# working.net
KiCad netlist of a schematic drawn in EAGLE
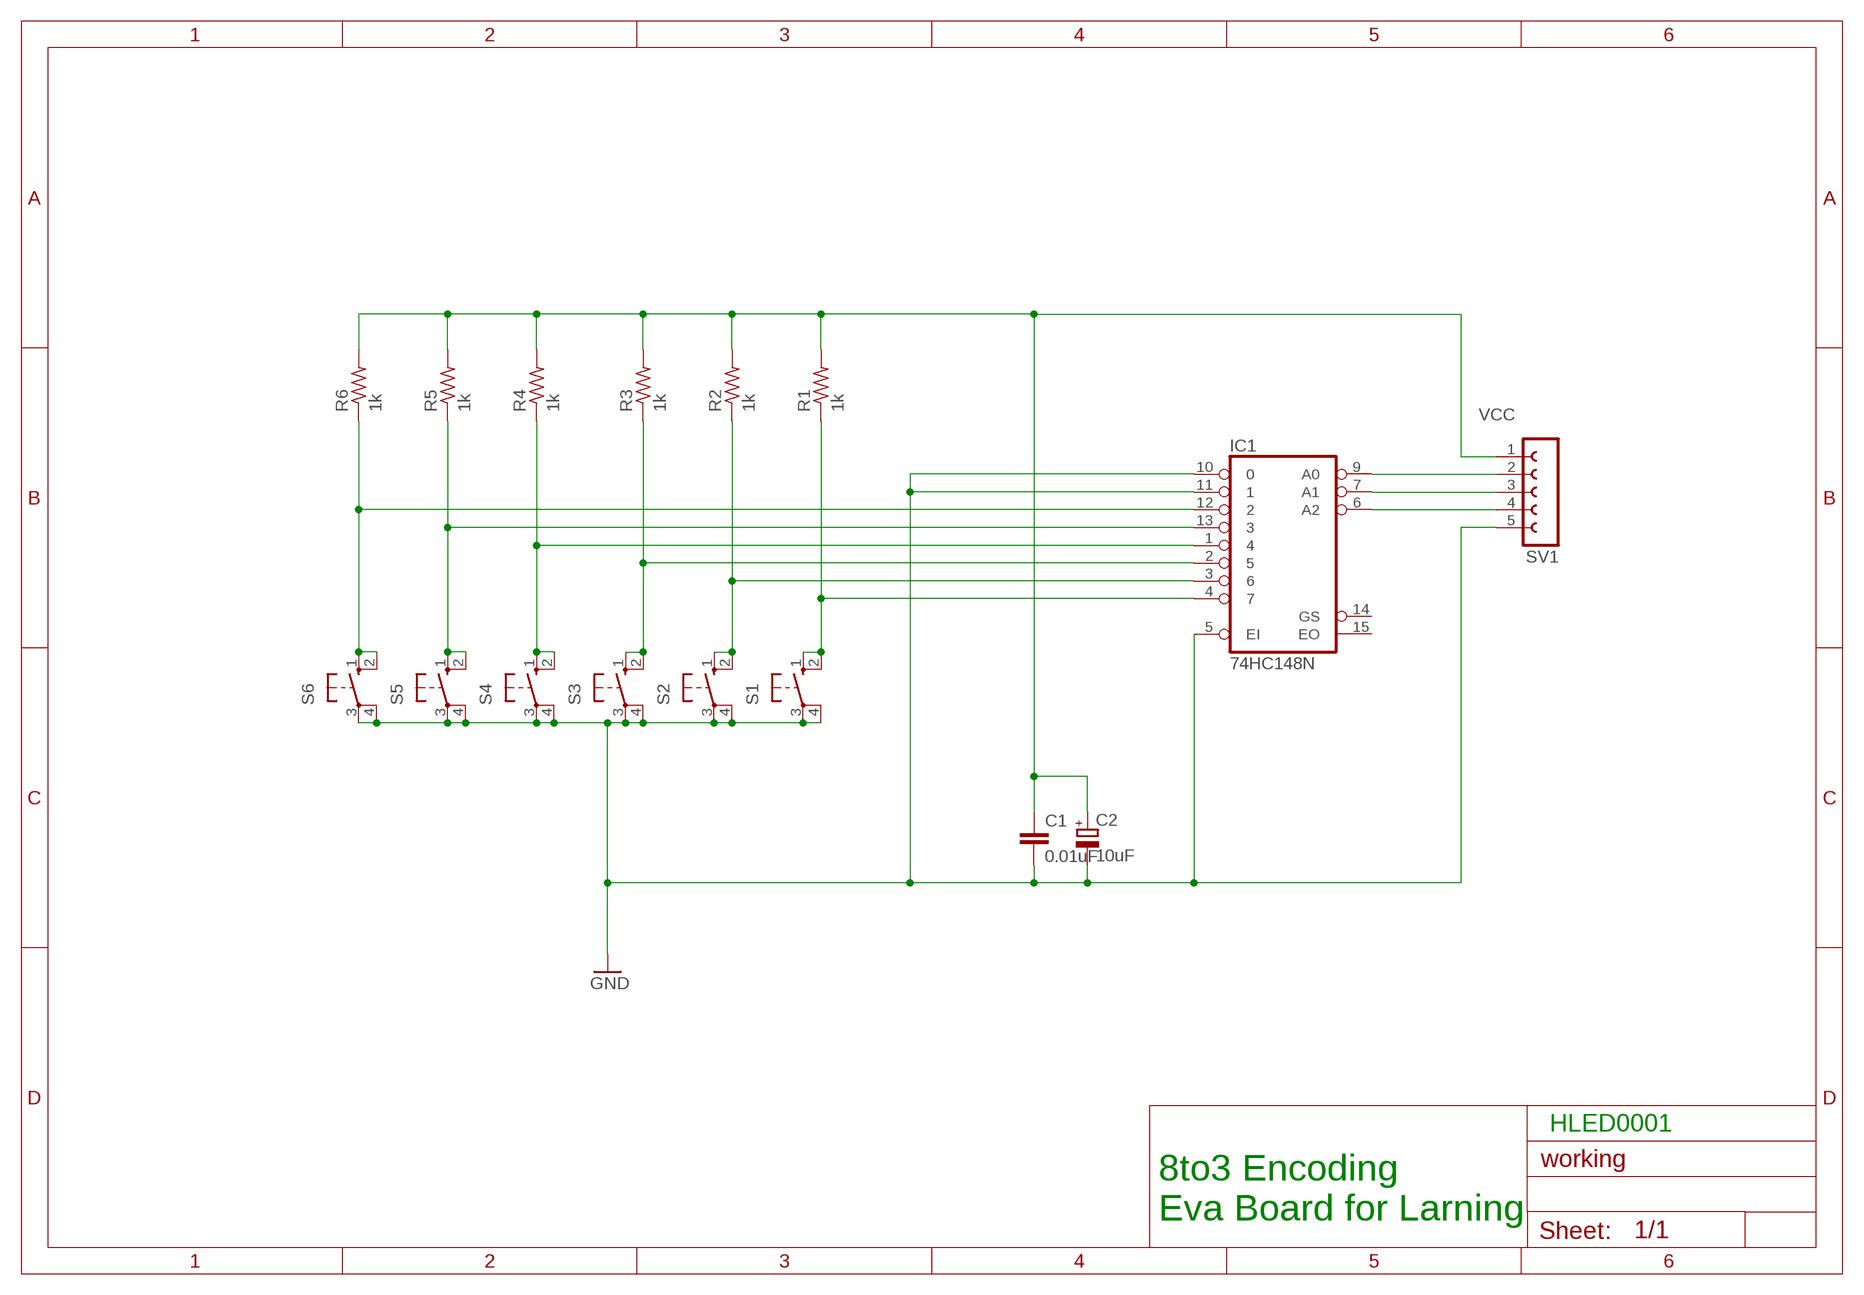
[diagram p0: schematic, sheet 1]

(export (version "E")
  (design (tool "Eeschema 10.0.6"))
  (components
    (comp (ref "C1")
      (value "0.01uF")
      (footprint "eagle-import:C025-025X050")
      (libsource (lib "eagle-import") (part "C-EU025-025X050"))
    )
    (comp (ref "C2")
      (value "10uF")
      (footprint "eagle-import:E2,5-6E")
      (libsource (lib "eagle-import") (part "CPOL-EUE2,5-6E"))
    )
    (comp (ref "IC1")
      (value "74HC148N")
      (footprint "eagle-import:DIL16")
      (libsource (lib "eagle-import") (part "74148NHC"))
    )
    (comp (ref "R1")
      (value "1k")
      (footprint "eagle-import:0207_7")
      (libsource (lib "eagle-import") (part "R-US_0207/7"))
    )
    (comp (ref "R2")
      (value "1k")
      (footprint "eagle-import:0207_7")
      (libsource (lib "eagle-import") (part "R-US_0207/7"))
    )
    (comp (ref "R3")
      (value "1k")
      (footprint "eagle-import:0207_7")
      (libsource (lib "eagle-import") (part "R-US_0207/7"))
    )
    (comp (ref "R4")
      (value "1k")
      (footprint "eagle-import:0207_7")
      (libsource (lib "eagle-import") (part "R-US_0207/7"))
    )
    (comp (ref "R5")
      (value "1k")
      (footprint "eagle-import:0207_7")
      (libsource (lib "eagle-import") (part "R-US_0207/7"))
    )
    (comp (ref "R6")
      (value "1k")
      (footprint "eagle-import:0207_7")
      (libsource (lib "eagle-import") (part "R-US_0207/7"))
    )
    (comp (ref "S1")
      (value "10-XX")
      (footprint "eagle-import:B3F-10XX")
      (libsource (lib "eagle-import") (part "10-XX"))
    )
    (comp (ref "S2")
      (value "10-XX")
      (footprint "eagle-import:B3F-10XX")
      (libsource (lib "eagle-import") (part "10-XX"))
    )
    (comp (ref "S3")
      (value "10-XX")
      (footprint "eagle-import:B3F-10XX")
      (libsource (lib "eagle-import") (part "10-XX"))
    )
    (comp (ref "S4")
      (value "10-XX")
      (footprint "eagle-import:B3F-10XX")
      (libsource (lib "eagle-import") (part "10-XX"))
    )
    (comp (ref "S5")
      (value "10-XX")
      (footprint "eagle-import:B3F-10XX")
      (libsource (lib "eagle-import") (part "10-XX"))
    )
    (comp (ref "S6")
      (value "10-XX")
      (footprint "eagle-import:B3F-10XX")
      (libsource (lib "eagle-import") (part "10-XX"))
    )
    (comp (ref "SV1")
      (value "FE05-1")
      (footprint "eagle-import:FE05-1")
      (libsource (lib "eagle-import") (part "FE05-1"))
    )
  )
  (nets
    (net (code "1") (name "/VCC") (class "Default")
      (node (ref "C1") (pin "1") (pinfunction "1_1") (pintype "passive"))
      (node (ref "C2") (pin "+") (pinfunction "+_+") (pintype "passive"))
      (node (ref "R1") (pin "2") (pinfunction "2_2") (pintype "passive"))
      (node (ref "R2") (pin "2") (pinfunction "2_2") (pintype "passive"))
      (node (ref "R3") (pin "2") (pinfunction "2_2") (pintype "passive"))
      (node (ref "R4") (pin "2") (pinfunction "2_2") (pintype "passive"))
      (node (ref "R5") (pin "2") (pinfunction "2_2") (pintype "passive"))
      (node (ref "R6") (pin "2") (pinfunction "2_2") (pintype "passive"))
      (node (ref "SV1") (pin "1") (pinfunction "1_1") (pintype "passive"))
    )
    (net (code "2") (name "GND") (class "Default")
      (node (ref "C1") (pin "2") (pinfunction "2_2") (pintype "passive"))
      (node (ref "C2") (pin "-") (pinfunction "-_-") (pintype "passive"))
      (node (ref "IC1") (pin "10") (pinfunction "0_10") (pintype "input"))
      (node (ref "IC1") (pin "11") (pinfunction "1_11") (pintype "input"))
      (node (ref "IC1") (pin "5") (pinfunction "EI_5") (pintype "input"))
      (node (ref "S1") (pin "3") (pinfunction "P_3") (pintype "passive"))
      (node (ref "S1") (pin "4") (pinfunction "P1_4") (pintype "passive"))
      (node (ref "S2") (pin "3") (pinfunction "P_3") (pintype "passive"))
      (node (ref "S2") (pin "4") (pinfunction "P1_4") (pintype "passive"))
      (node (ref "S3") (pin "3") (pinfunction "P_3") (pintype "passive"))
      (node (ref "S3") (pin "4") (pinfunction "P1_4") (pintype "passive"))
      (node (ref "S4") (pin "3") (pinfunction "P_3") (pintype "passive"))
      (node (ref "S4") (pin "4") (pinfunction "P1_4") (pintype "passive"))
      (node (ref "S5") (pin "3") (pinfunction "P_3") (pintype "passive"))
      (node (ref "S5") (pin "4") (pinfunction "P1_4") (pintype "passive"))
      (node (ref "S6") (pin "3") (pinfunction "P_3") (pintype "passive"))
      (node (ref "S6") (pin "4") (pinfunction "P1_4") (pintype "passive"))
      (node (ref "SV1") (pin "5") (pinfunction "5_5") (pintype "passive"))
    )
    (net (code "3") (name "Net-(IC1A-2)") (class "Default")
      (node (ref "IC1") (pin "12") (pinfunction "2_12") (pintype "input"))
      (node (ref "R6") (pin "1") (pinfunction "1_1") (pintype "passive"))
      (node (ref "S6") (pin "1") (pinfunction "S_1") (pintype "passive"))
      (node (ref "S6") (pin "2") (pinfunction "S1_2") (pintype "passive"))
    )
    (net (code "4") (name "Net-(IC1A-3)") (class "Default")
      (node (ref "IC1") (pin "13") (pinfunction "3_13") (pintype "input"))
      (node (ref "R5") (pin "1") (pinfunction "1_1") (pintype "passive"))
      (node (ref "S5") (pin "1") (pinfunction "S_1") (pintype "passive"))
      (node (ref "S5") (pin "2") (pinfunction "S1_2") (pintype "passive"))
    )
    (net (code "5") (name "Net-(IC1A-4)") (class "Default")
      (node (ref "IC1") (pin "1") (pinfunction "4_1") (pintype "input"))
      (node (ref "R4") (pin "1") (pinfunction "1_1") (pintype "passive"))
      (node (ref "S4") (pin "1") (pinfunction "S_1") (pintype "passive"))
      (node (ref "S4") (pin "2") (pinfunction "S1_2") (pintype "passive"))
    )
    (net (code "6") (name "Net-(IC1A-5)") (class "Default")
      (node (ref "IC1") (pin "2") (pinfunction "5_2") (pintype "input"))
      (node (ref "R3") (pin "1") (pinfunction "1_1") (pintype "passive"))
      (node (ref "S3") (pin "1") (pinfunction "S_1") (pintype "passive"))
      (node (ref "S3") (pin "2") (pinfunction "S1_2") (pintype "passive"))
    )
    (net (code "7") (name "Net-(IC1A-6)") (class "Default")
      (node (ref "IC1") (pin "3") (pinfunction "6_3") (pintype "input"))
      (node (ref "R2") (pin "1") (pinfunction "1_1") (pintype "passive"))
      (node (ref "S2") (pin "1") (pinfunction "S_1") (pintype "passive"))
      (node (ref "S2") (pin "2") (pinfunction "S1_2") (pintype "passive"))
    )
    (net (code "8") (name "Net-(IC1A-7)") (class "Default")
      (node (ref "IC1") (pin "4") (pinfunction "7_4") (pintype "input"))
      (node (ref "R1") (pin "1") (pinfunction "1_1") (pintype "passive"))
      (node (ref "S1") (pin "1") (pinfunction "S_1") (pintype "passive"))
      (node (ref "S1") (pin "2") (pinfunction "S1_2") (pintype "passive"))
    )
    (net (code "9") (name "Net-(IC1A-A0)") (class "Default")
      (node (ref "IC1") (pin "9") (pinfunction "A0_9") (pintype "output"))
      (node (ref "SV1") (pin "2") (pinfunction "2_2") (pintype "passive"))
    )
    (net (code "10") (name "Net-(IC1A-A1)") (class "Default")
      (node (ref "IC1") (pin "7") (pinfunction "A1_7") (pintype "output"))
      (node (ref "SV1") (pin "3") (pinfunction "3_3") (pintype "passive"))
    )
    (net (code "11") (name "Net-(IC1A-A2)") (class "Default")
      (node (ref "IC1") (pin "6") (pinfunction "A2_6") (pintype "output"))
      (node (ref "SV1") (pin "4") (pinfunction "4_4") (pintype "passive"))
    )
    (net (code "12") (name "unconnected-(IC1A-EO-Pad15)") (class "Default")
      (node (ref "IC1") (pin "15") (pinfunction "EO_15") (pintype "output"))
    )
    (net (code "13") (name "unconnected-(IC1A-GS-Pad14)") (class "Default")
      (node (ref "IC1") (pin "14") (pinfunction "GS_14") (pintype "output"))
    )
  )
)
